# Top.net
KiCad netlist of a schematic drawn in Altium Designer
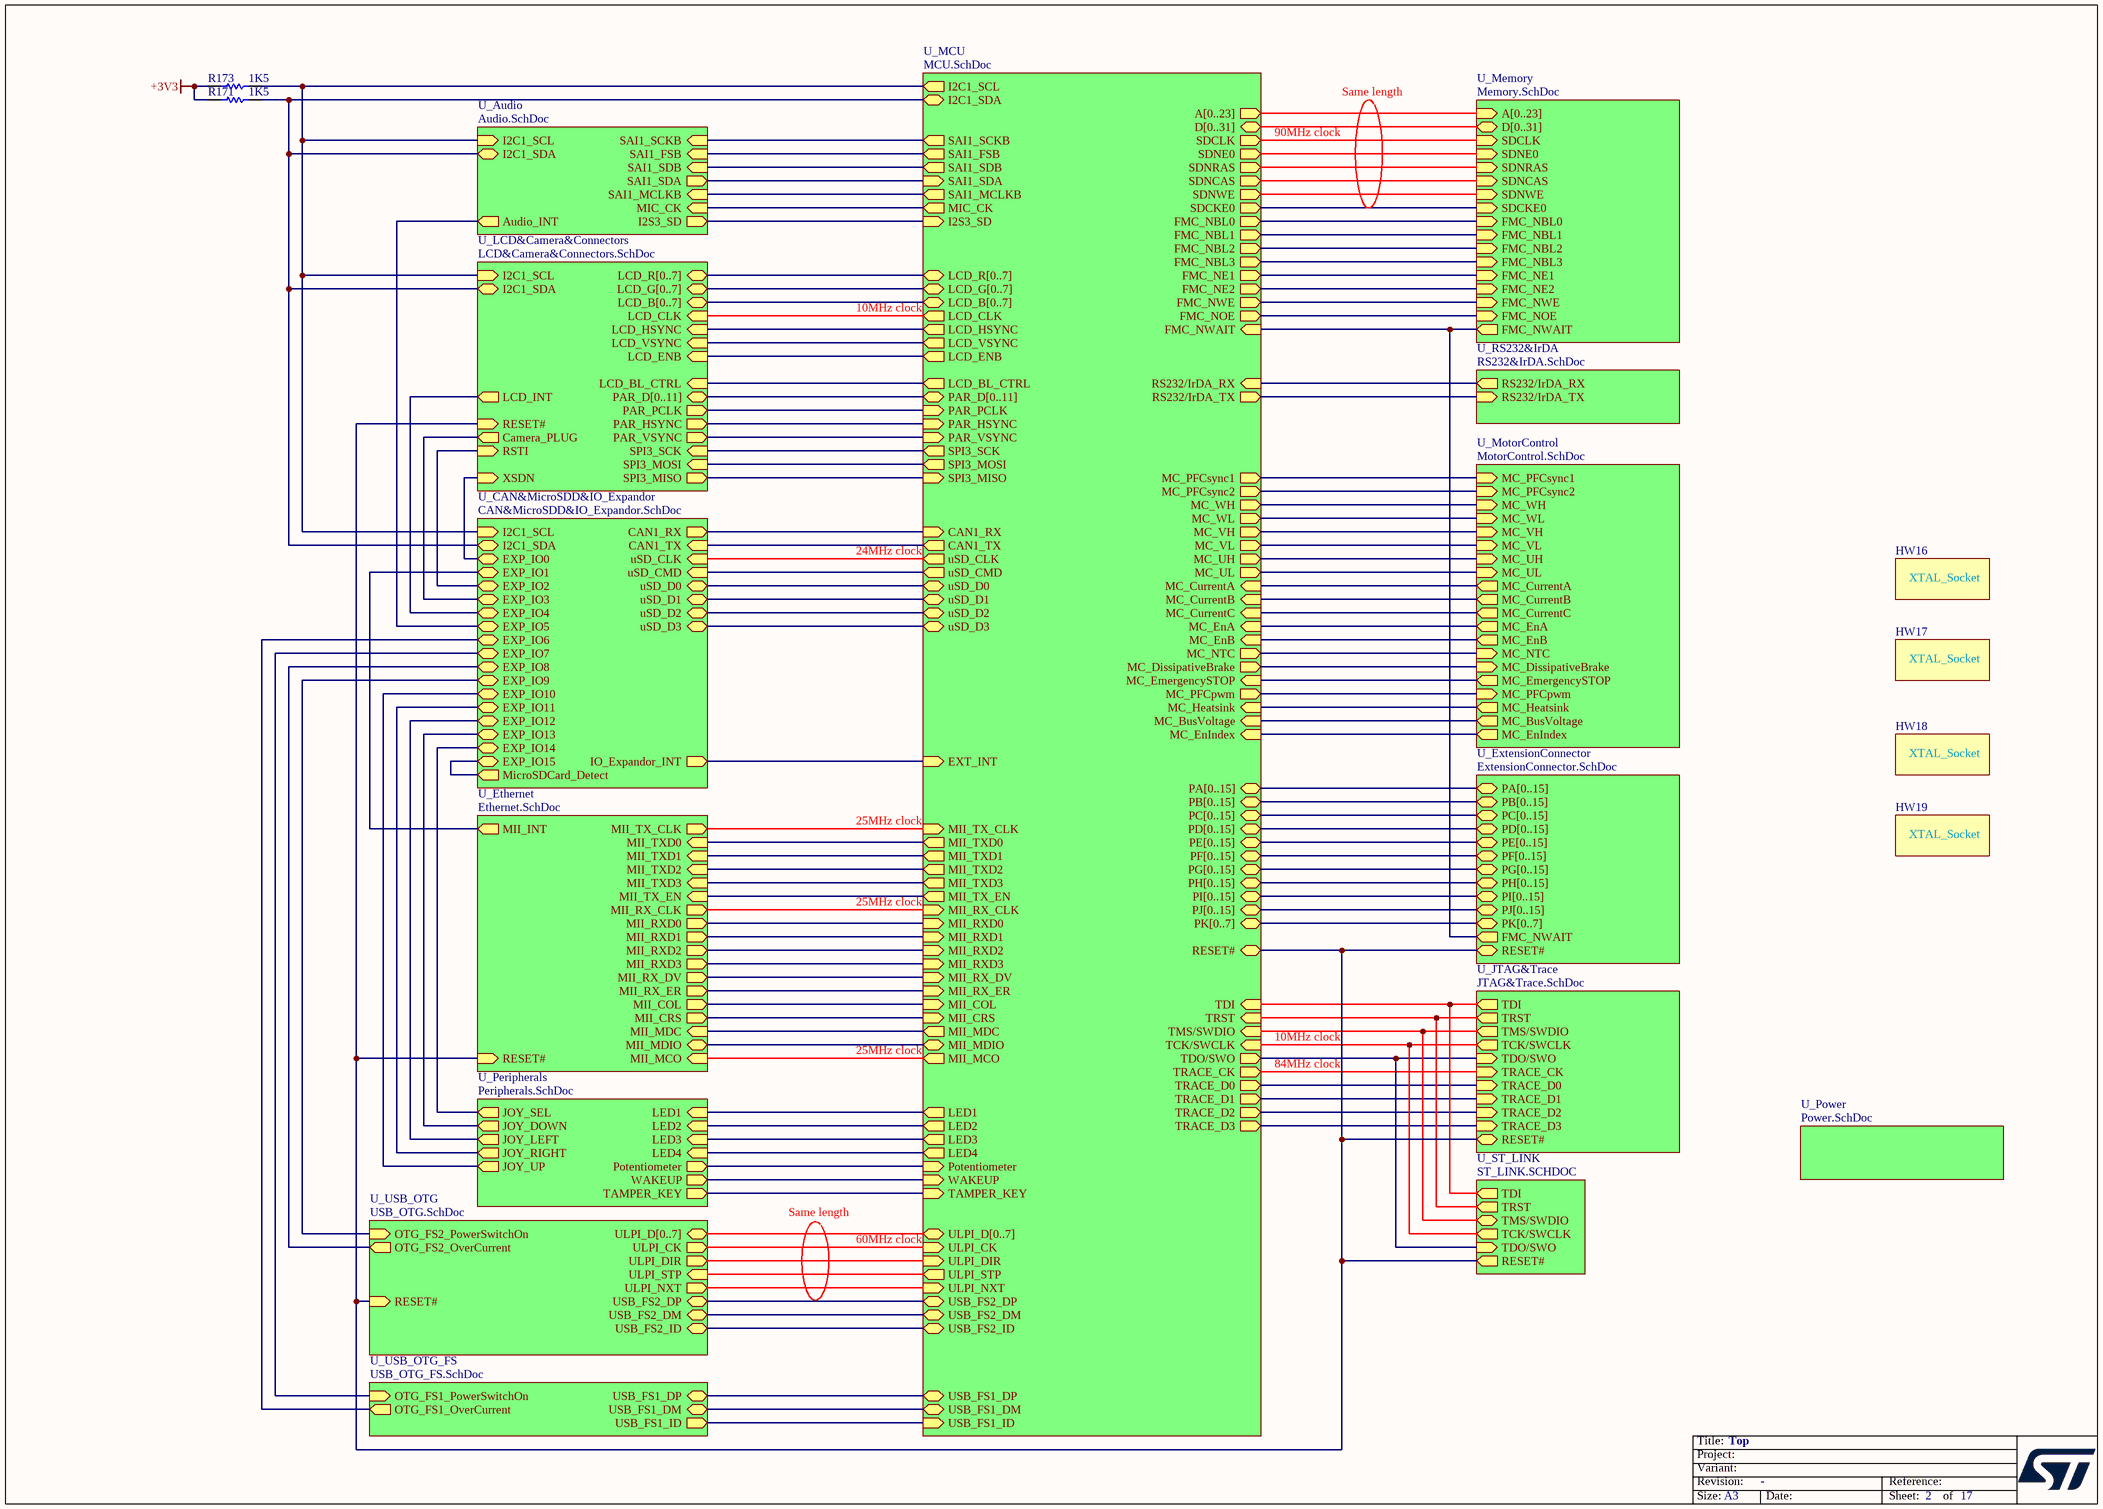
[diagram p0: Top.SchDoc]

(export (version "E")
  (design (tool "Eeschema 10.0.6"))
  (components
    (comp (ref "HW16") (value "~") (libsource (lib "mb1045") (part "XTAL_Socket")))
    (comp (ref "HW17") (value "~") (libsource (lib "mb1045") (part "XTAL_Socket")))
    (comp (ref "HW18") (value "~") (libsource (lib "mb1045") (part "XTAL_Socket")))
    (comp (ref "HW19") (value "~") (libsource (lib "mb1045") (part "XTAL_Socket")))
    (comp (ref "R171")
      (value "1K5")
      (footprint "0603R")
      (description "Resistor")
      (fields (field (name "PUBLISHER") "Altium Limited"))
      (libsource (lib "Miscellaneous Devices") (part "Res1"))
    )
    (comp (ref "R173")
      (value "1K5")
      (footprint "0603R")
      (description "Resistor")
      (fields (field (name "PUBLISHER") "Altium Limited"))
      (libsource (lib "Miscellaneous Devices") (part "Res1"))
    )
  )
  (nets
    (net (code "1") (name "+3V3") (class "Default")
      (node (ref "R171") (pin "1") (pinfunction "1_1") (pintype "passive"))
      (node (ref "R173") (pin "1") (pinfunction "1_1") (pintype "passive"))
    )
    (net (code "21") (name "/I2C1_SCL") (class "Default")
      (node (ref "R173") (pin "2") (pinfunction "2_2") (pintype "passive"))
    )
    (net (code "22") (name "/I2C1_SDA") (class "Default")
      (node (ref "R171") (pin "2") (pinfunction "2_2") (pintype "passive"))
    )
  )
)
